# Input.net
KiCad netlist of a schematic drawn in Altium Designer
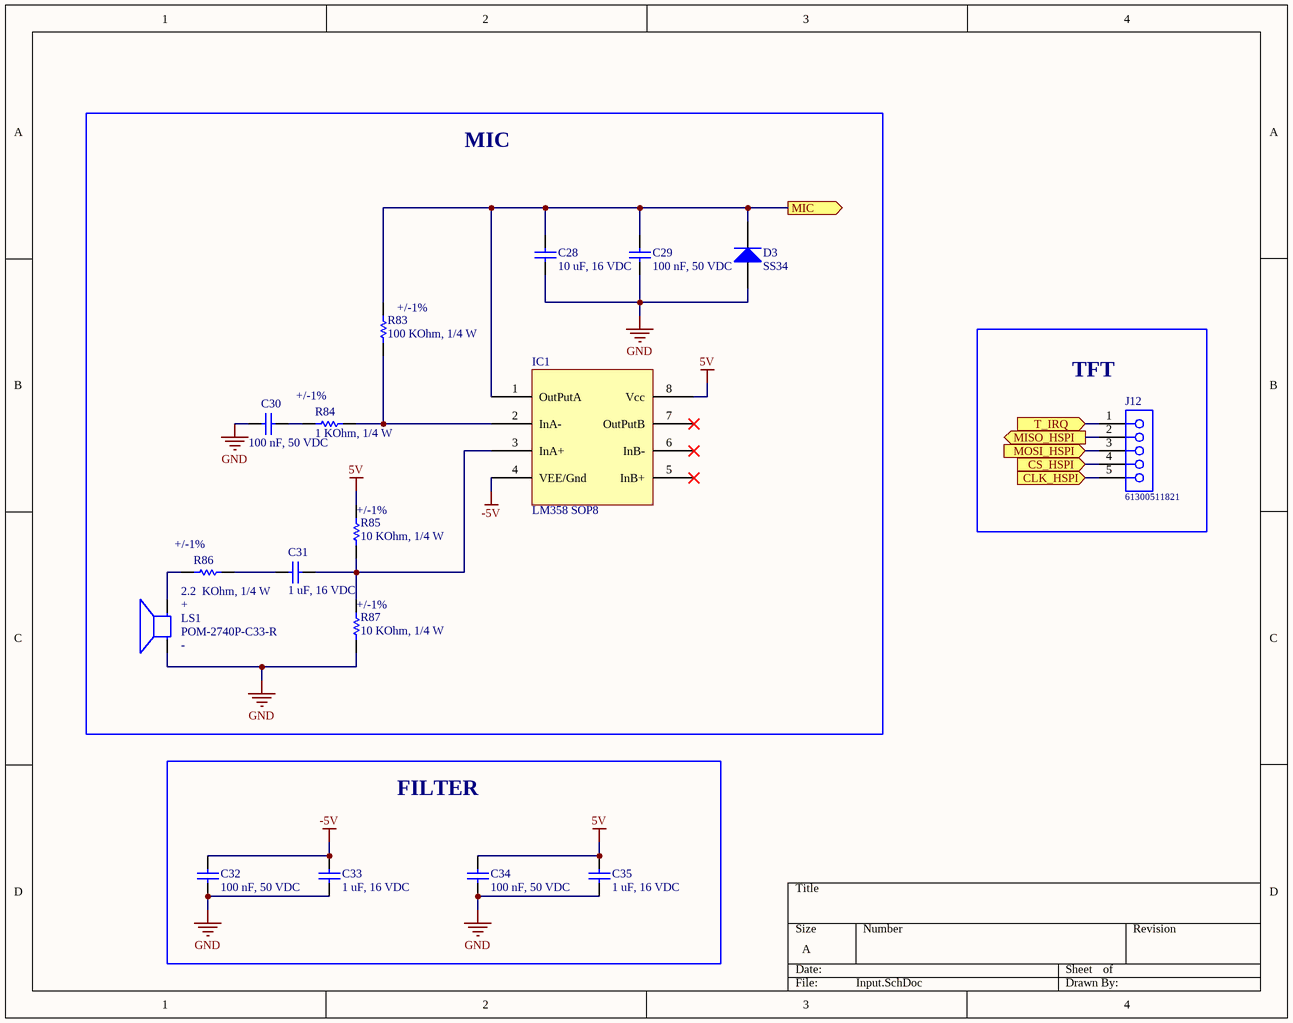
[diagram p0: Input.SchDoc]

(export (version "E")
  (design (tool "Eeschema 10.0.6"))
  (components
    (comp (ref "C28")
      (value "10 uF, 16 VDC")
      (footprint "CAP_0603")
      (description "CAP, size 0603, 10 uF, 16 VDC")
      (fields (field (name "TOLERANCE") "+/-10%"))
      (libsource (lib "Altium_Ceramic_Cap") (part "0106031061010"))
    )
    (comp (ref "C29")
      (value "100 nF, 50 VDC")
      (footprint "CAP_0603")
      (description "CAP, size 0603, 100 nF, 50 VDC")
      (fields (field (name "TOLERANCE") "+/-10%"))
      (libsource (lib "Altium_Ceramic_Cap") (part "0106031041050"))
    )
    (comp (ref "C30")
      (value "100 nF, 50 VDC")
      (footprint "CAP_0603")
      (description "CAP, size 0603, 100 nF, 50 VDC")
      (fields (field (name "TOLERANCE") "+/-10%"))
      (libsource (lib "Altium_Ceramic_Cap") (part "0106031041050"))
    )
    (comp (ref "C31")
      (value "1 uF, 16 VDC")
      (footprint "CAP_0603")
      (description "CAP, size 0603, 1 uF, 16 VDC")
      (fields (field (name "TOLERANCE") "+/-10%"))
      (libsource (lib "Altium_Ceramic_Cap") (part "0106031051016"))
    )
    (comp (ref "C32")
      (value "100 nF, 50 VDC")
      (footprint "CAP_0603")
      (description "CAP, size 0603, 100 nF, 50 VDC")
      (fields (field (name "TOLERANCE") "+/-10%"))
      (libsource (lib "Altium_Ceramic_Cap") (part "0106031041050"))
    )
    (comp (ref "C33")
      (value "1 uF, 16 VDC")
      (footprint "CAP_0603")
      (description "CAP, size 0603, 1 uF, 16 VDC")
      (fields (field (name "TOLERANCE") "+/-10%"))
      (libsource (lib "Altium_Ceramic_Cap") (part "0106031051016"))
    )
    (comp (ref "C34")
      (value "100 nF, 50 VDC")
      (footprint "CAP_0603")
      (description "CAP, size 0603, 100 nF, 50 VDC")
      (fields (field (name "TOLERANCE") "+/-10%"))
      (libsource (lib "Altium_Ceramic_Cap") (part "0106031041050"))
    )
    (comp (ref "C35")
      (value "1 uF, 16 VDC")
      (footprint "CAP_0603")
      (description "CAP, size 0603, 1 uF, 16 VDC")
      (fields (field (name "TOLERANCE") "+/-10%"))
      (libsource (lib "Altium_Ceramic_Cap") (part "0106031051016"))
    )
    (comp (ref "D3")
      (value "SS34")
      (footprint "DIODE SMA")
      (description "Dán")
      (libsource (lib "Diode") (part "Diode SS34 ( 1N5822 )"))
    )
    (comp (ref "IC1")
      (value "LM358 SOP8")
      (footprint "SOP 8")
      (description "Dán")
      (libsource (lib "IC") (part "LM358 SOP8"))
    )
    (comp (ref "J12")
      (value "61300511821")
      (footprint "61300511821")
      (description "WR-PHD Socket Header, THT, pitch 2.54mm, Single Row, Vertical, 5p")
      (fields (field (name "MANUFACTURER") "Wurth Elektronik"))
      (libsource (lib "Altium_Header") (part "61300511821"))
    )
    (comp (ref "LS1")
      (value "POM-2740P-C33-R")
      (footprint "MIC_POM-2740P-C33-R")
      (description "MICROPHONE -40DB 2VDC")
      (fields (field (name "MF") "PUI Audio"))
      (libsource (lib "POM-2740P-C33-R") (part "POM-2740P-C33-R"))
    )
    (comp (ref "R83")
      (value "100 KOhm, 1/4 W")
      (footprint "resistor_0603")
      (description "RES, size 0603, 100 KOhm, 1/4 W")
      (fields (field (name "RESISTANCE TOLERANCE") "+/-1%"))
      (libsource (lib "Altium_Resistor") (part "0006031041"))
    )
    (comp (ref "R84")
      (value "1 KOhm, 1/4 W")
      (footprint "resistor_0603")
      (description "RES, size 0603, 1 KOhm, 1/4 W")
      (fields (field (name "RESISTANCE TOLERANCE") "+/-1%"))
      (libsource (lib "Altium_Resistor") (part "0006031021"))
    )
    (comp (ref "R85")
      (value "10 KOhm, 1/4 W")
      (footprint "resistor_0603")
      (description "RES, size 0603, 10 KOhm, 1/4 W")
      (fields (field (name "RESISTANCE TOLERANCE") "+/-1%"))
      (libsource (lib "Altium_Resistor") (part "0006031031"))
    )
    (comp (ref "R86")
      (value "2.2  KOhm, 1/4 W")
      (footprint "resistor_0603")
      (description "RES, size 0603, 2.2  KOhm, 1/4 W")
      (fields (field (name "RESISTANCE TOLERANCE") "+/-1%"))
      (libsource (lib "Altium_Resistor") (part "0006032221"))
    )
    (comp (ref "R87")
      (value "10 KOhm, 1/4 W")
      (footprint "resistor_0603")
      (description "RES, size 0603, 10 KOhm, 1/4 W")
      (fields (field (name "RESISTANCE TOLERANCE") "+/-1%"))
      (libsource (lib "Altium_Resistor") (part "0006031031"))
    )
  )
  (nets
    (net (code "1") (name "-5V") (class "Default")
      (node (ref "C32") (pin "2") (pinfunction "2_2") (pintype "passive"))
      (node (ref "C33") (pin "2") (pinfunction "2_2") (pintype "passive"))
      (node (ref "IC1") (pin "4") (pinfunction "VEE/Gnd_4") (pintype "passive"))
    )
    (net (code "2") (name "/CLK_HSPI") (class "Default")
      (node (ref "J12") (pin "5") (pinfunction "5_5") (pintype "passive"))
    )
    (net (code "3") (name "/CS_HSPI") (class "Default")
      (node (ref "J12") (pin "4") (pinfunction "4_4") (pintype "passive"))
    )
    (net (code "4") (name "/MIC") (class "Default")
      (node (ref "C28") (pin "2") (pinfunction "2_2") (pintype "passive"))
      (node (ref "C29") (pin "2") (pinfunction "2_2") (pintype "passive"))
      (node (ref "D3") (pin "2") (pinfunction "K_2") (pintype "passive"))
      (node (ref "IC1") (pin "1") (pinfunction "OutPutA_1") (pintype "passive"))
      (node (ref "R83") (pin "2") (pinfunction "2_2") (pintype "passive"))
    )
    (net (code "5") (name "/MISO_HSPI") (class "Default")
      (node (ref "J12") (pin "2") (pinfunction "2_2") (pintype "passive"))
    )
    (net (code "6") (name "/MOSI_HSPI") (class "Default")
      (node (ref "J12") (pin "3") (pinfunction "3_3") (pintype "passive"))
    )
    (net (code "7") (name "/T_IRQ") (class "Default")
      (node (ref "J12") (pin "1") (pinfunction "1_1") (pintype "passive"))
    )
    (net (code "8") (name "5V") (class "Default")
      (node (ref "C34") (pin "2") (pinfunction "2_2") (pintype "passive"))
      (node (ref "C35") (pin "2") (pinfunction "2_2") (pintype "passive"))
      (node (ref "IC1") (pin "8") (pinfunction "Vcc_8") (pintype "passive"))
      (node (ref "R85") (pin "2") (pinfunction "2_2") (pintype "passive"))
    )
    (net (code "9") (name "GND") (class "Default")
      (node (ref "C28") (pin "1") (pinfunction "1_1") (pintype "passive"))
      (node (ref "C29") (pin "1") (pinfunction "1_1") (pintype "passive"))
      (node (ref "C30") (pin "2") (pinfunction "2_2") (pintype "passive"))
      (node (ref "C32") (pin "1") (pinfunction "1_1") (pintype "passive"))
      (node (ref "C33") (pin "1") (pinfunction "1_1") (pintype "passive"))
      (node (ref "C34") (pin "1") (pinfunction "1_1") (pintype "passive"))
      (node (ref "C35") (pin "1") (pinfunction "1_1") (pintype "passive"))
      (node (ref "D3") (pin "1") (pinfunction "A_1") (pintype "passive"))
      (node (ref "LS1") (pin "N") (pinfunction "NEG_N") (pintype "passive"))
      (node (ref "R87") (pin "1") (pinfunction "1_1") (pintype "passive"))
    )
    (net (code "10") (name "Net-(C30-Pad1)") (class "Default")
      (node (ref "C30") (pin "1") (pinfunction "1_1") (pintype "passive"))
      (node (ref "R84") (pin "1") (pinfunction "1_1") (pintype "passive"))
    )
    (net (code "11") (name "Net-(C31-Pad2)") (class "Default")
      (node (ref "C31") (pin "2") (pinfunction "2_2") (pintype "passive"))
      (node (ref "R86") (pin "2") (pinfunction "2_2") (pintype "passive"))
    )
    (net (code "12") (name "Net-(IC1-InA+)") (class "Default")
      (node (ref "C31") (pin "1") (pinfunction "1_1") (pintype "passive"))
      (node (ref "IC1") (pin "3") (pinfunction "InA+_3") (pintype "passive"))
      (node (ref "R85") (pin "1") (pinfunction "1_1") (pintype "passive"))
      (node (ref "R87") (pin "2") (pinfunction "2_2") (pintype "passive"))
    )
    (net (code "13") (name "Net-(IC1-InA-)") (class "Default")
      (node (ref "IC1") (pin "2") (pinfunction "InA-_2") (pintype "passive"))
      (node (ref "R83") (pin "1") (pinfunction "1_1") (pintype "passive"))
      (node (ref "R84") (pin "2") (pinfunction "2_2") (pintype "passive"))
    )
    (net (code "14") (name "Net-(LS1-POS)") (class "Default")
      (node (ref "LS1") (pin "P") (pinfunction "POS_P") (pintype "passive"))
      (node (ref "R86") (pin "1") (pinfunction "1_1") (pintype "passive"))
    )
    (net (code "15") (name "unconnected-(IC1-InB+-Pad5)") (class "Default")
      (node (ref "IC1") (pin "5") (pinfunction "InB+_5") (pintype "passive+no_connect"))
    )
    (net (code "16") (name "unconnected-(IC1-InB--Pad6)") (class "Default")
      (node (ref "IC1") (pin "6") (pinfunction "InB-_6") (pintype "passive+no_connect"))
    )
    (net (code "17") (name "unconnected-(IC1-OutPutB-Pad7)") (class "Default")
      (node (ref "IC1") (pin "7") (pinfunction "OutPutB_7") (pintype "passive+no_connect"))
    )
  )
)
